# soldering_station.net
KiCad netlist of a schematic drawn in EAGLE
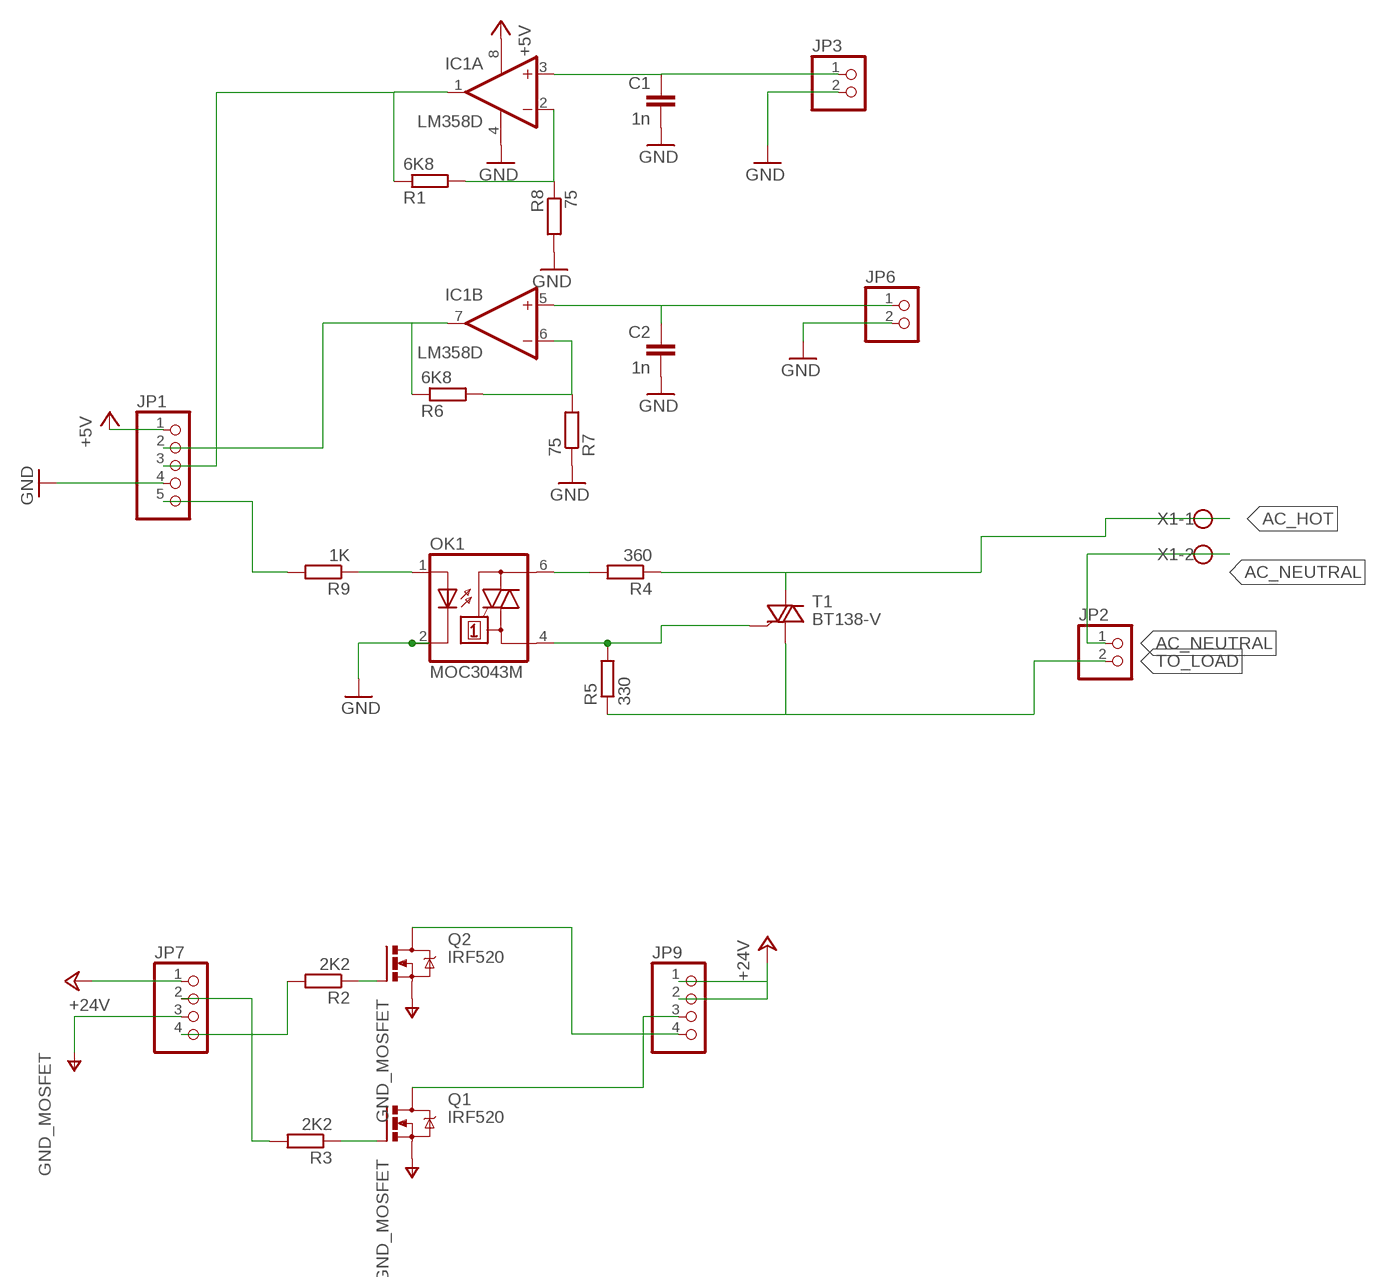
[diagram p0: schematic, sheet 1]

(export (version "E")
  (design (tool "Eeschema 10.0.6"))
  (components
    (comp (ref "C1")
      (value "1n")
      (footprint "eagle-import:C0805")
      (libsource (lib "eagle-import") (part "C-EUC0805"))
    )
    (comp (ref "C2")
      (value "1n")
      (footprint "eagle-import:C0805")
      (libsource (lib "eagle-import") (part "C-EUC0805"))
    )
    (comp (ref "IC1")
      (value "LM358D")
      (footprint "eagle-import:SO08")
      (libsource (lib "eagle-import") (part "LM358D"))
    )
    (comp (ref "JP1")
      (value "PINHD-1X5")
      (footprint "eagle-import:1X05")
      (libsource (lib "eagle-import") (part "PINHD-1X5"))
    )
    (comp (ref "JP2")
      (value "PINHD-1X2")
      (footprint "eagle-import:1X02")
      (libsource (lib "eagle-import") (part "PINHD-1X2"))
    )
    (comp (ref "JP3")
      (value "PINHD-1X2")
      (footprint "eagle-import:1X02")
      (libsource (lib "eagle-import") (part "PINHD-1X2"))
    )
    (comp (ref "JP6")
      (value "PINHD-1X2")
      (footprint "eagle-import:1X02")
      (libsource (lib "eagle-import") (part "PINHD-1X2"))
    )
    (comp (ref "JP7")
      (value "PINHD-1X4")
      (footprint "eagle-import:1X04")
      (libsource (lib "eagle-import") (part "PINHD-1X4"))
    )
    (comp (ref "JP9")
      (value "PINHD-1X4")
      (footprint "eagle-import:1X04")
      (libsource (lib "eagle-import") (part "PINHD-1X4"))
    )
    (comp (ref "OK1")
      (value "MOC3043M")
      (footprint "eagle-import:DIL06")
      (fields (field (name "MF") "FAIRCHILD SEMICONDUCTOR") (field (name "MPN") "MOC3043-M"))
      (libsource (lib "eagle-import") (part "MOC3043M"))
    )
    (comp (ref "Q1")
      (value "IRF520")
      (footprint "eagle-import:TO220BV")
      (libsource (lib "eagle-import") (part "IRF520"))
    )
    (comp (ref "Q2")
      (value "IRF520")
      (footprint "eagle-import:TO220BV")
      (libsource (lib "eagle-import") (part "IRF520"))
    )
    (comp (ref "R1")
      (value "6K8")
      (footprint "eagle-import:R0805")
      (libsource (lib "eagle-import") (part "R-EU_R0805"))
    )
    (comp (ref "R2")
      (value "2K2")
      (footprint "eagle-import:R0805")
      (libsource (lib "eagle-import") (part "R-EU_R0805"))
    )
    (comp (ref "R3")
      (value "2K2")
      (footprint "eagle-import:R0805")
      (libsource (lib "eagle-import") (part "R-EU_R0805"))
    )
    (comp (ref "R4")
      (value "360")
      (footprint "eagle-import:R0805")
      (libsource (lib "eagle-import") (part "R-EU_R0805"))
    )
    (comp (ref "R5")
      (value "330")
      (footprint "eagle-import:R0805")
      (libsource (lib "eagle-import") (part "R-EU_R0805"))
    )
    (comp (ref "R6")
      (value "6K8")
      (footprint "eagle-import:R0805")
      (libsource (lib "eagle-import") (part "R-EU_R0805"))
    )
    (comp (ref "R7")
      (value "75")
      (footprint "eagle-import:R0805")
      (libsource (lib "eagle-import") (part "R-EU_R0805"))
    )
    (comp (ref "R8")
      (value "75")
      (footprint "eagle-import:R0805")
      (libsource (lib "eagle-import") (part "R-EU_R0805"))
    )
    (comp (ref "R9")
      (value "1K")
      (footprint "eagle-import:R0805")
      (libsource (lib "eagle-import") (part "R-EU_R0805"))
    )
    (comp (ref "T1")
      (value "BT138-V")
      (footprint "eagle-import:TO220BV")
      (libsource (lib "eagle-import") (part "BT138-V"))
    )
    (comp (ref "X1")
      (value "W237-102")
      (footprint "eagle-import:W237-102")
      (fields (field (name "MPN") "237-102"))
      (libsource (lib "eagle-import") (part "W237-102"))
    )
  )
  (nets
    (net (code "1") (name "+5V") (class "Default")
      (node (ref "IC1") (pin "8") (pinfunction "V+_8") (pintype "power_in"))
      (node (ref "JP1") (pin "1") (pinfunction "1_1") (pintype "passive"))
    )
    (net (code "2") (name "+24V") (class "Default")
      (node (ref "JP7") (pin "1") (pinfunction "1_1") (pintype "passive"))
      (node (ref "JP9") (pin "1") (pinfunction "1_1") (pintype "passive"))
      (node (ref "JP9") (pin "2") (pinfunction "2_2") (pintype "passive"))
    )
    (net (code "3") (name "AC_HOT") (class "Default")
      (node (ref "R4") (pin "1") (pinfunction "1_1") (pintype "passive"))
      (node (ref "T1") (pin "T2") (pinfunction "A2_T2") (pintype "passive"))
      (node (ref "X1") (pin "1") (pinfunction "KL_1") (pintype "passive"))
    )
    (net (code "4") (name "AC_NEUTRAL") (class "Default")
      (node (ref "JP2") (pin "1") (pinfunction "1_1") (pintype "passive"))
      (node (ref "X1") (pin "2") (pinfunction "KL_2") (pintype "passive"))
    )
    (net (code "5") (name "GND") (class "Default")
      (node (ref "C1") (pin "2") (pinfunction "2_2") (pintype "passive"))
      (node (ref "C2") (pin "2") (pinfunction "2_2") (pintype "passive"))
      (node (ref "IC1") (pin "4") (pinfunction "V-_4") (pintype "power_in"))
      (node (ref "JP1") (pin "4") (pinfunction "4_4") (pintype "passive"))
      (node (ref "JP3") (pin "2") (pinfunction "2_2") (pintype "passive"))
      (node (ref "JP6") (pin "2") (pinfunction "2_2") (pintype "passive"))
      (node (ref "OK1") (pin "2") (pinfunction "C_2") (pintype "passive"))
      (node (ref "R7") (pin "1") (pinfunction "1_1") (pintype "passive"))
      (node (ref "R8") (pin "2") (pinfunction "2_2") (pintype "passive"))
    )
    (net (code "6") (name "GND_MOSFET") (class "Default")
      (node (ref "JP7") (pin "3") (pinfunction "3_3") (pintype "passive"))
      (node (ref "Q1") (pin "S") (pinfunction "S_S") (pintype "passive"))
      (node (ref "Q2") (pin "S") (pinfunction "S_S") (pintype "passive"))
    )
    (net (code "7") (name "Net-(IC1A-+IN)") (class "Default")
      (node (ref "C1") (pin "1") (pinfunction "1_1") (pintype "passive"))
      (node (ref "IC1") (pin "3") (pinfunction "+IN_3") (pintype "input"))
      (node (ref "JP3") (pin "1") (pinfunction "1_1") (pintype "passive"))
    )
    (net (code "8") (name "Net-(IC1A--IN)") (class "Default")
      (node (ref "IC1") (pin "2") (pinfunction "-IN_2") (pintype "input"))
      (node (ref "R1") (pin "2") (pinfunction "2_2") (pintype "passive"))
      (node (ref "R8") (pin "1") (pinfunction "1_1") (pintype "passive"))
    )
    (net (code "9") (name "Net-(IC1A-OUT)") (class "Default")
      (node (ref "IC1") (pin "1") (pinfunction "OUT_1") (pintype "output"))
      (node (ref "JP1") (pin "3") (pinfunction "3_3") (pintype "passive"))
      (node (ref "R1") (pin "1") (pinfunction "1_1") (pintype "passive"))
    )
    (net (code "10") (name "Net-(IC1B-+IN)") (class "Default")
      (node (ref "C2") (pin "1") (pinfunction "1_1") (pintype "passive"))
      (node (ref "IC1") (pin "5") (pinfunction "+IN_5") (pintype "input"))
      (node (ref "JP6") (pin "1") (pinfunction "1_1") (pintype "passive"))
    )
    (net (code "11") (name "Net-(IC1B--IN)") (class "Default")
      (node (ref "IC1") (pin "6") (pinfunction "-IN_6") (pintype "input"))
      (node (ref "R6") (pin "2") (pinfunction "2_2") (pintype "passive"))
      (node (ref "R7") (pin "2") (pinfunction "2_2") (pintype "passive"))
    )
    (net (code "12") (name "Net-(IC1B-OUT)") (class "Default")
      (node (ref "IC1") (pin "7") (pinfunction "OUT_7") (pintype "output"))
      (node (ref "JP1") (pin "2") (pinfunction "2_2") (pintype "passive"))
      (node (ref "R6") (pin "1") (pinfunction "1_1") (pintype "passive"))
    )
    (net (code "13") (name "Net-(JP1-Pad5)") (class "Default")
      (node (ref "JP1") (pin "5") (pinfunction "5_5") (pintype "passive"))
      (node (ref "R9") (pin "2") (pinfunction "2_2") (pintype "passive"))
    )
    (net (code "14") (name "Net-(JP7-Pad2)") (class "Default")
      (node (ref "JP7") (pin "2") (pinfunction "2_2") (pintype "passive"))
      (node (ref "R3") (pin "2") (pinfunction "2_2") (pintype "passive"))
    )
    (net (code "15") (name "Net-(JP7-Pad4)") (class "Default")
      (node (ref "JP7") (pin "4") (pinfunction "4_4") (pintype "passive"))
      (node (ref "R2") (pin "2") (pinfunction "2_2") (pintype "passive"))
    )
    (net (code "16") (name "Net-(JP9-Pad3)") (class "Default")
      (node (ref "JP9") (pin "3") (pinfunction "3_3") (pintype "passive"))
      (node (ref "Q1") (pin "D") (pinfunction "D_D") (pintype "passive"))
    )
    (net (code "17") (name "Net-(JP9-Pad4)") (class "Default")
      (node (ref "JP9") (pin "4") (pinfunction "4_4") (pintype "passive"))
      (node (ref "Q2") (pin "D") (pinfunction "D_D") (pintype "passive"))
    )
    (net (code "18") (name "Net-(OK1-A)") (class "Default")
      (node (ref "OK1") (pin "1") (pinfunction "A_1") (pintype "passive"))
      (node (ref "R9") (pin "1") (pinfunction "1_1") (pintype "passive"))
    )
    (net (code "19") (name "Net-(OK1-A1)") (class "Default")
      (node (ref "OK1") (pin "4") (pinfunction "A1_4") (pintype "passive"))
      (node (ref "R5") (pin "2") (pinfunction "2_2") (pintype "passive"))
      (node (ref "T1") (pin "G") (pinfunction "G_G") (pintype "passive"))
    )
    (net (code "20") (name "Net-(OK1-A2)") (class "Default")
      (node (ref "OK1") (pin "6") (pinfunction "A2_6") (pintype "passive"))
      (node (ref "R4") (pin "2") (pinfunction "2_2") (pintype "passive"))
    )
    (net (code "21") (name "Net-(Q1-PadG)") (class "Default")
      (node (ref "Q1") (pin "G") (pinfunction "G_G") (pintype "passive"))
      (node (ref "R3") (pin "1") (pinfunction "1_1") (pintype "passive"))
    )
    (net (code "22") (name "Net-(Q2-PadG)") (class "Default")
      (node (ref "Q2") (pin "G") (pinfunction "G_G") (pintype "passive"))
      (node (ref "R2") (pin "1") (pinfunction "1_1") (pintype "passive"))
    )
    (net (code "23") (name "TO_LOAD") (class "Default")
      (node (ref "JP2") (pin "2") (pinfunction "2_2") (pintype "passive"))
      (node (ref "R5") (pin "1") (pinfunction "1_1") (pintype "passive"))
      (node (ref "T1") (pin "T1") (pinfunction "A1_T1") (pintype "passive"))
    )
  )
)
